# Communication.net
KiCad netlist of a schematic drawn in Altium Designer
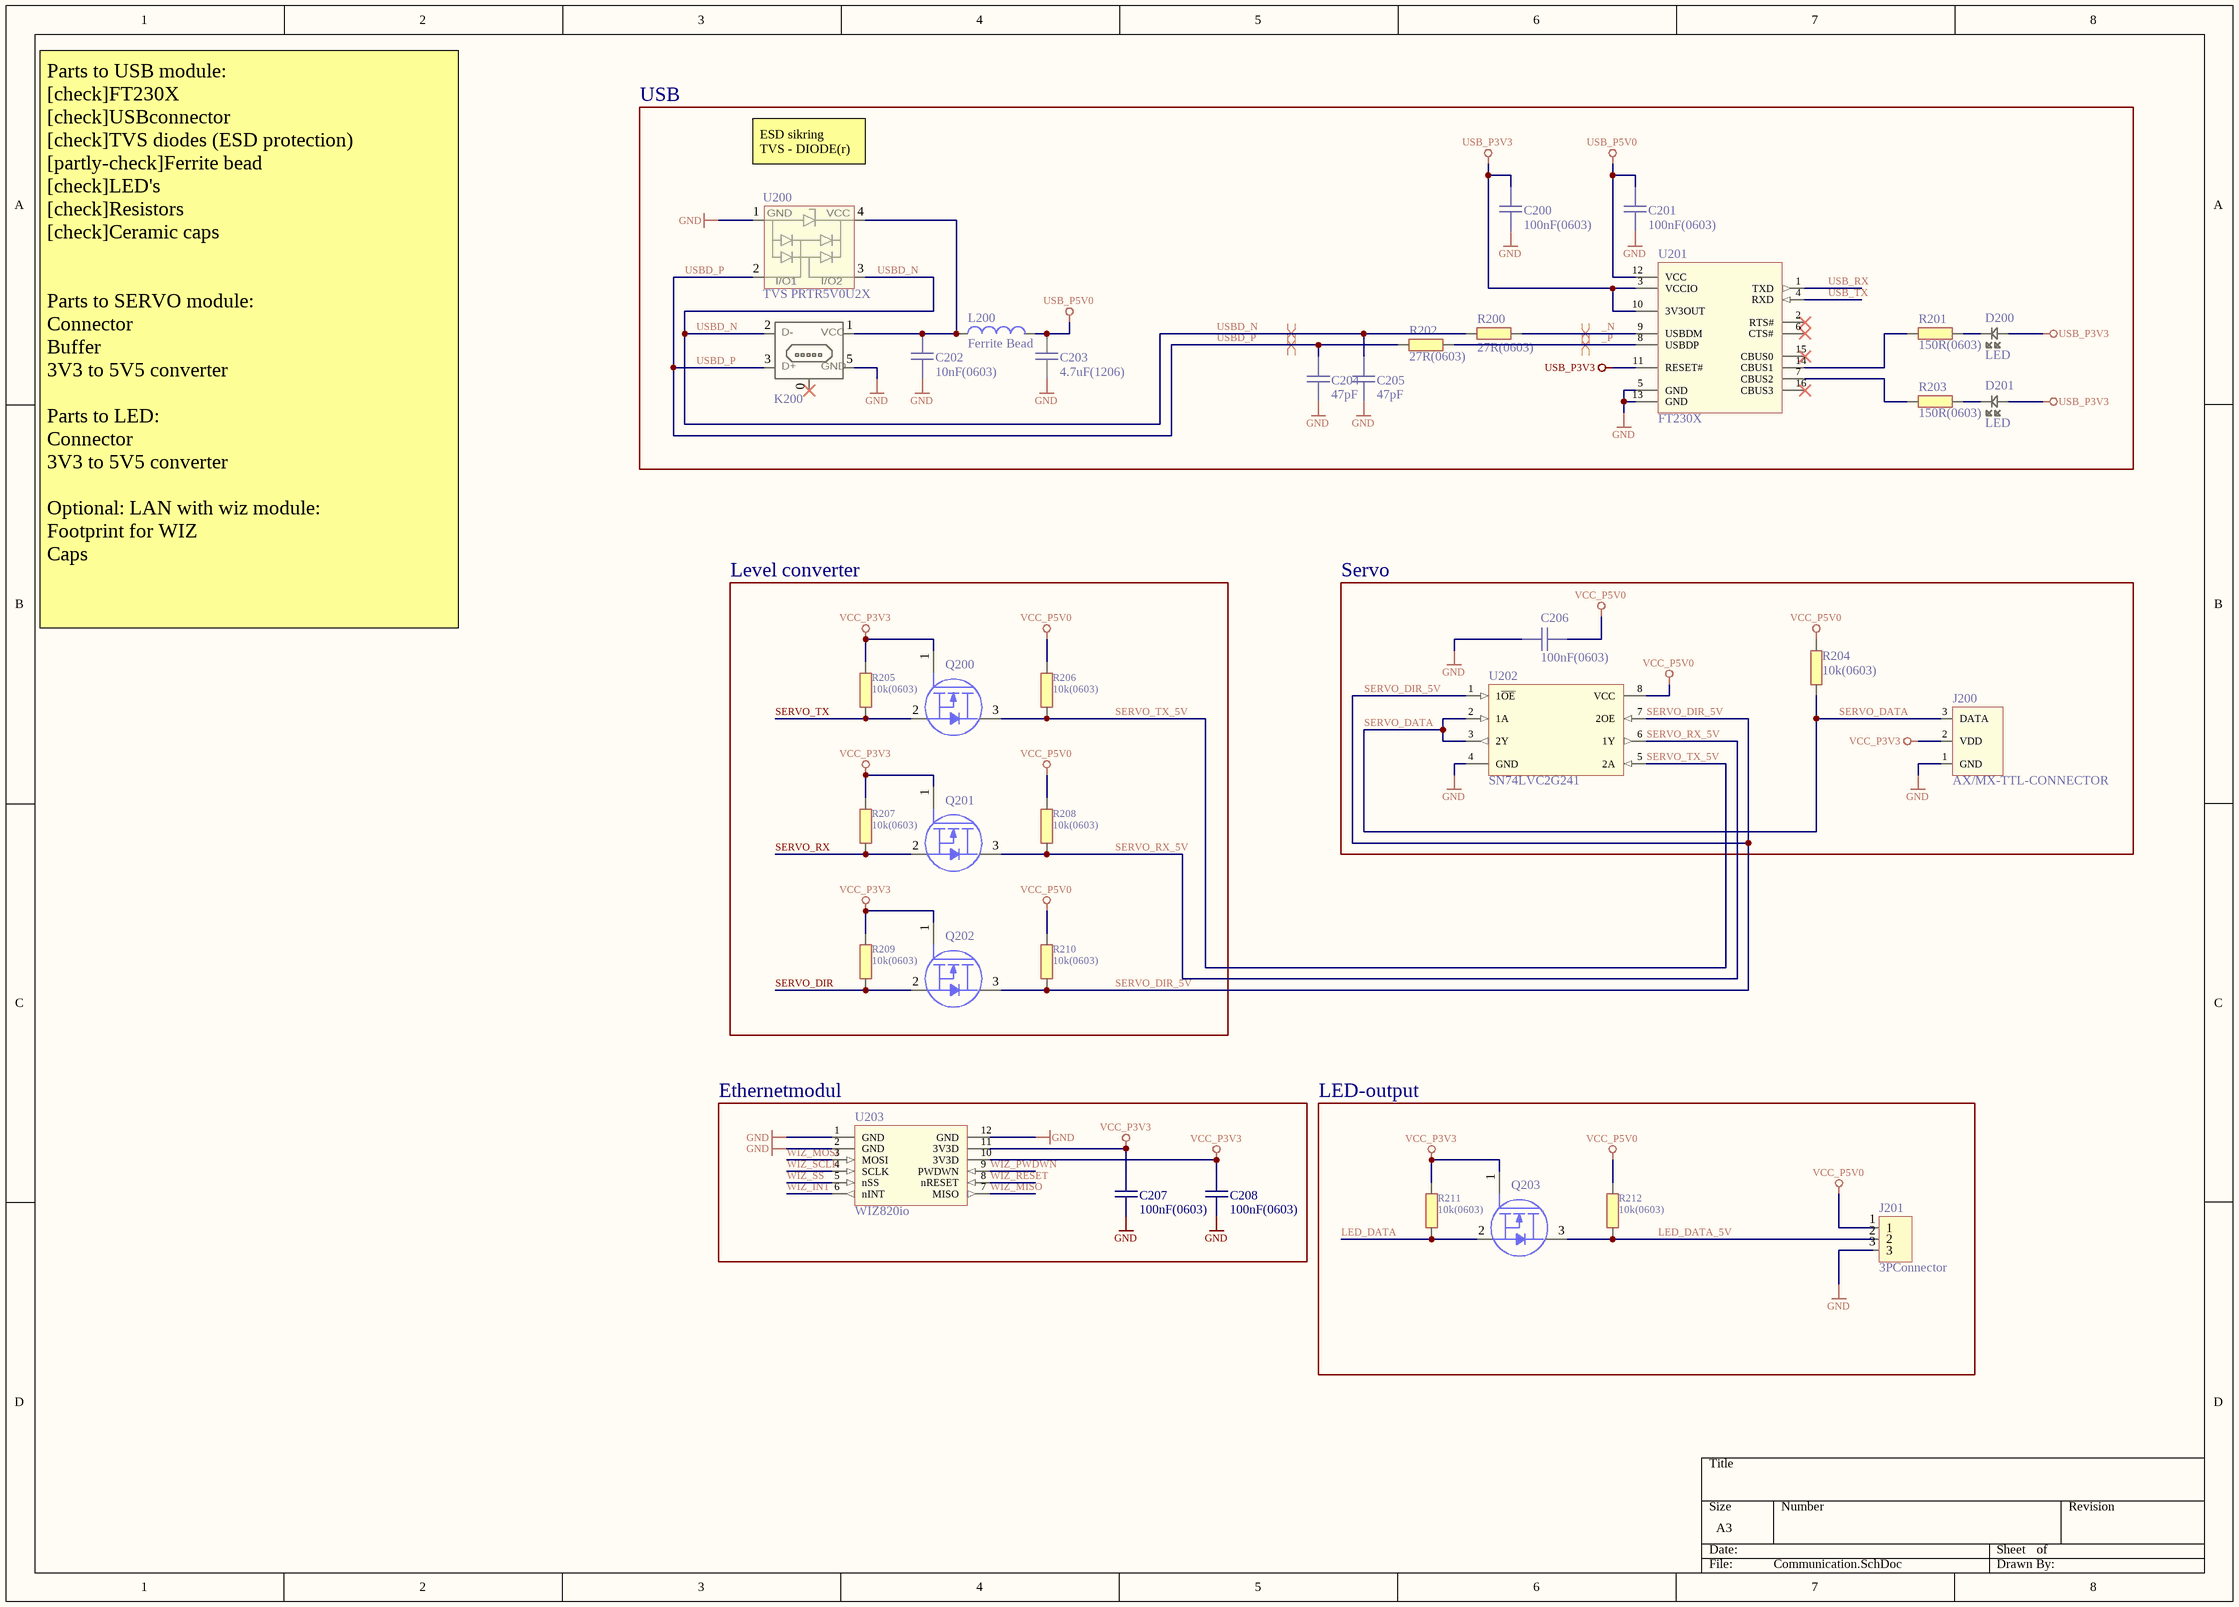
[diagram p0: Communication.SchDoc]

(export (version "E")
  (design (tool "Eeschema 10.0.6"))
  (components
    (comp (ref "C200")
      (value "100nF(0603)")
      (footprint "CAPC0603(1608)55_N")
      (description "100nF 0603 5% X7R 50V")
      (libsource (lib "OVLib") (part "CAP"))
    )
    (comp (ref "C201")
      (value "100nF(0603)")
      (footprint "CAPC0603(1608)55_N")
      (description "100nF 0603 5% X7R 50V")
      (libsource (lib "OVLib") (part "CAP"))
    )
    (comp (ref "C202")
      (value "10nF(0603)")
      (footprint "CAPC0603(1608)55_N")
      (description "0603 5% NP0 50V")
      (libsource (lib "OVLib") (part "CAP"))
    )
    (comp (ref "C203")
      (value "4.7uF(1206)")
      (footprint "CAPC1206(3216)170_N")
      (description "1206 chip X7R 50V")
      (libsource (lib "OVLib") (part "CAP"))
    )
    (comp (ref "C204")
      (value "47pF")
      (footprint "CAPC0603(1608)55_N")
      (description "0603 5% NP0 50V")
      (libsource (lib "OVLib") (part "CAP"))
    )
    (comp (ref "C205")
      (value "47pF")
      (footprint "CAPC0603(1608)55_N")
      (description "0603 5% NP0 50V")
      (libsource (lib "OVLib") (part "CAP"))
    )
    (comp (ref "C206")
      (value "100nF(0603)")
      (footprint "CAPC0603(1608)55_N")
      (description "100nF 0603 5% X7R 50V")
      (libsource (lib "OVLib") (part "CAP"))
    )
    (comp (ref "C207")
      (value "100nF(0603)")
      (footprint "CAPC0603(1608)55_N")
      (description "100nF 0603 5% X7R 50V")
      (libsource (lib "OVLib") (part "CAP"))
    )
    (comp (ref "C208")
      (value "100nF(0603)")
      (footprint "CAPC0603(1608)55_N")
      (description "100nF 0603 5% X7R 50V")
      (libsource (lib "OVLib") (part "CAP"))
    )
    (comp (ref "D200")
      (value "LED")
      (footprint "I_LEDC0603(1608)_N")
      (description "SMD")
      (libsource (lib "OVLib") (part "LED"))
    )
    (comp (ref "D201")
      (value "LED")
      (footprint "I_LEDC0603(1608)_N")
      (description "SMD")
      (libsource (lib "OVLib") (part "LED"))
    )
    (comp (ref "J200")
      (value "AX/MX-TTL-CONNECTOR")
      (footprint "MOLEX_22-03-5035")
      (description "Dynamixel AX/MX-Series servo connector 3 pin TTL version")
      (fields (field (name "MPN") "22-03-5035"))
      (libsource (lib "AX_MX-TTL-CONNECTOR") (part "AX/MX-TTL-CONNECTOR"))
    )
    (comp (ref "J201")
      (value "3PConnector")
      (footprint "JST_3P")
      (description "pris pr. stk.")
      (libsource (lib "OVLib") (part "3PConnector"))
    )
    (comp (ref "K200")
      (value "USB-OTG")
      (footprint "MILL-MAX_897-43-005-00-100001")
      (description "MINI USB B DEVICE CONNECTOR MOLEX 51387-0571")
      (fields
        (field (name "MANUFACTURER") "Mill-Max Manufacturing Corp.")
        (field (name "MPN") "897-43-005-00-100001")
      )
      (libsource (lib "MILL-MAX_897-43-005-00-100001") (part "MILL-MAX_897-43-005-00-100001"))
    )
    (comp (ref "L200")
      (value "Ferrite Bead")
      (footprint "0603")
      (description "Ferrite Bead 0603")
      (fields (field (name "MPN") "BLM18SG331TN1D"))
      (libsource (lib "BLM18SG331TN1D") (part "BLM18SG331TN1D"))
    )
    (comp (ref "Q200")
      (value "MOSFET_N_GSD")
      (footprint "SOT323P130X100-3_N")
      (description "N-Channel MOSFET 300mA")
      (libsource (lib "OVLib") (part "MOSFET_N_GSD"))
    )
    (comp (ref "Q201")
      (value "MOSFET_N_GSD")
      (footprint "SOT323P130X100-3_N")
      (description "N-Channel MOSFET 300mA")
      (libsource (lib "OVLib") (part "MOSFET_N_GSD"))
    )
    (comp (ref "Q202")
      (value "MOSFET_N_GSD")
      (footprint "SOT323P130X100-3_N")
      (description "N-Channel MOSFET 300mA")
      (libsource (lib "OVLib") (part "MOSFET_N_GSD"))
    )
    (comp (ref "Q203")
      (value "MOSFET_N_GSD")
      (footprint "SOT323P130X100-3_N")
      (description "N-Channel MOSFET 300mA")
      (libsource (lib "OVLib") (part "MOSFET_N_GSD"))
    )
    (comp (ref "R200")
      (value "27R(0603)")
      (footprint "RESC0603(1608)_N")
      (description "0603 0.1W 1% Thick film resistor")
      (libsource (lib "") (part "Resistor2_2"))
    )
    (comp (ref "R201")
      (value "150R(0603)")
      (footprint "RESC0603(1608)_N")
      (description "0603 0.1W 1% Thick film resistor")
      (libsource (lib "") (part "Resistor2_3"))
    )
    (comp (ref "R202")
      (value "27R(0603)")
      (footprint "RESC0603(1608)_N")
      (description "0603 0.1W 1% Thick film resistor")
      (libsource (lib "") (part "Resistor2_2"))
    )
    (comp (ref "R203")
      (value "150R(0603)")
      (footprint "RESC0603(1608)_N")
      (description "0603 0.1W 1% Thick film resistor")
      (libsource (lib "") (part "Resistor2_3"))
    )
    (comp (ref "R204")
      (value "10k(0603)")
      (footprint "RESC0603(1608)_N")
      (description "10k 0603 0.1W 1% Thick film resistor")
      (libsource (lib "OVLib") (part "Resistor2"))
    )
    (comp (ref "R205")
      (value "10k(0603)")
      (footprint "RESC0603(1608)_N")
      (description "10k 0603 0.1W 1% Thick film resistor")
      (libsource (lib "") (part "Resistor2_1"))
    )
    (comp (ref "R206")
      (value "10k(0603)")
      (footprint "RESC0603(1608)_N")
      (description "10k 0603 0.1W 1% Thick film resistor")
      (libsource (lib "") (part "Resistor2_1"))
    )
    (comp (ref "R207")
      (value "10k(0603)")
      (footprint "RESC0603(1608)_N")
      (description "10k 0603 0.1W 1% Thick film resistor")
      (libsource (lib "") (part "Resistor2_1"))
    )
    (comp (ref "R208")
      (value "10k(0603)")
      (footprint "RESC0603(1608)_N")
      (description "10k 0603 0.1W 1% Thick film resistor")
      (libsource (lib "") (part "Resistor2_1"))
    )
    (comp (ref "R209")
      (value "10k(0603)")
      (footprint "RESC0603(1608)_N")
      (description "10k 0603 0.1W 1% Thick film resistor")
      (libsource (lib "") (part "Resistor2_1"))
    )
    (comp (ref "R210")
      (value "10k(0603)")
      (footprint "RESC0603(1608)_N")
      (description "10k 0603 0.1W 1% Thick film resistor")
      (libsource (lib "") (part "Resistor2_1"))
    )
    (comp (ref "R211")
      (value "10k(0603)")
      (footprint "RESC0603(1608)_N")
      (description "10k 0603 0.1W 1% Thick film resistor")
      (libsource (lib "") (part "Resistor2_1"))
    )
    (comp (ref "R212")
      (value "10k(0603)")
      (footprint "RESC0603(1608)_N")
      (description "10k 0603 0.1W 1% Thick film resistor")
      (libsource (lib "") (part "Resistor2_1"))
    )
    (comp (ref "U200")
      (value "TVS PRTR5V0U2X")
      (footprint "SOT143B-M")
      (description "TVS Didode dual PRTR5V0U2X")
      (fields (field (name "MPN") "PRTR5V0U2X") (field (name "MANUFACTURER") "NXP"))
      (libsource (lib "PRTR5V0U2X") (part "PRTR5V0U2X"))
    )
    (comp (ref "U201")
      (value "FT230X")
      (footprint "SOP0635P4800-16N")
      (description "IC USB SERIAL BASIC UART 16SSOP")
      (fields
        (field (name "MPN") "FT230XS-R")
        (field (name "MANUFACTURER") "FTDI, Future Technology Devices International Ltd")
      )
      (libsource (lib "FT230XS") (part "FT230X"))
    )
    (comp (ref "U202")
      (value "SN74LVC2G241")
      (footprint "TSOP65P400X130-8N")
      (description "Dual  Buffer/Driver  With  3-State  Outputs, designed for 1.65-5.5Vcc operation")
      (fields (field (name "MANUFACTURER") "Texas Instruments") (field (name "MPN") "SN74LVC2G241DCUR"))
      (libsource (lib "SN74LVC2G241") (part "SN74LVC2G241"))
    )
    (comp (ref "U203")
      (value "WIZ820io")
      (footprint "Wiz820io")
      (description "WIZ820io, Ethernet module with W5200 module onboard and MAG-JACK")
      (fields (field (name "MPN") "WIZ820IO") (field (name "MANUFACTURER") "WIZnet"))
      (libsource (lib "WIZ820io") (part "WIZ820io"))
    )
  )
  (nets
    (net (code "1") (name "/LED_DATA") (class "Default")
      (node (ref "Q203") (pin "2") (pinfunction "Source_2") (pintype "passive"))
      (node (ref "R211") (pin "2") (pinfunction "2_2") (pintype "passive"))
    )
    (net (code "2") (name "/LED_DATA_5V") (class "Default")
      (node (ref "J201") (pin "2") (pinfunction "2_2") (pintype "passive"))
      (node (ref "Q203") (pin "3") (pinfunction "Drain_3") (pintype "passive"))
      (node (ref "R212") (pin "2") (pinfunction "2_2") (pintype "passive"))
    )
    (net (code "3") (name "/SERVO_DATA") (class "Default")
      (node (ref "J200") (pin "3") (pinfunction "DATA_3") (pintype "passive"))
      (node (ref "R204") (pin "1") (pinfunction "1_1") (pintype "passive"))
      (node (ref "U202") (pin "2") (pinfunction "1A_2") (pintype "input"))
      (node (ref "U202") (pin "3") (pinfunction "2Y_3") (pintype "output"))
    )
    (net (code "4") (name "/SERVO_DIR") (class "Default")
      (node (ref "Q202") (pin "2") (pinfunction "Source_2") (pintype "passive"))
      (node (ref "R209") (pin "2") (pinfunction "2_2") (pintype "passive"))
    )
    (net (code "5") (name "/SERVO_DIR_5V") (class "Default")
      (node (ref "Q202") (pin "3") (pinfunction "Drain_3") (pintype "passive"))
      (node (ref "R210") (pin "2") (pinfunction "2_2") (pintype "passive"))
      (node (ref "U202") (pin "1") (pinfunction "1~{OE}_1") (pintype "input"))
      (node (ref "U202") (pin "7") (pinfunction "2OE_7") (pintype "input"))
    )
    (net (code "6") (name "/SERVO_RX") (class "Default")
      (node (ref "Q201") (pin "2") (pinfunction "Source_2") (pintype "passive"))
      (node (ref "R207") (pin "2") (pinfunction "2_2") (pintype "passive"))
    )
    (net (code "7") (name "/SERVO_RX_5V") (class "Default")
      (node (ref "Q201") (pin "3") (pinfunction "Drain_3") (pintype "passive"))
      (node (ref "R208") (pin "2") (pinfunction "2_2") (pintype "passive"))
      (node (ref "U202") (pin "6") (pinfunction "1Y_6") (pintype "output"))
    )
    (net (code "8") (name "/SERVO_TX") (class "Default")
      (node (ref "Q200") (pin "2") (pinfunction "Source_2") (pintype "passive"))
      (node (ref "R205") (pin "2") (pinfunction "2_2") (pintype "passive"))
    )
    (net (code "9") (name "/SERVO_TX_5V") (class "Default")
      (node (ref "Q200") (pin "3") (pinfunction "Drain_3") (pintype "passive"))
      (node (ref "R206") (pin "2") (pinfunction "2_2") (pintype "passive"))
      (node (ref "U202") (pin "5") (pinfunction "2A_5") (pintype "input"))
    )
    (net (code "10") (name "/USBD_N") (class "Default")
      (node (ref "C205") (pin "2") (pinfunction "2_2") (pintype "passive"))
      (node (ref "K200") (pin "2") (pinfunction "D-_2") (pintype "passive"))
      (node (ref "R200") (pin "1") (pinfunction "1_1") (pintype "passive"))
      (node (ref "U200") (pin "3") (pinfunction "I/O2_3") (pintype "passive"))
    )
    (net (code "11") (name "/USBD_P") (class "Default")
      (node (ref "C204") (pin "2") (pinfunction "2_2") (pintype "passive"))
      (node (ref "K200") (pin "3") (pinfunction "D+_3") (pintype "passive"))
      (node (ref "R202") (pin "1") (pinfunction "1_1") (pintype "passive"))
      (node (ref "U200") (pin "2") (pinfunction "I/O1_2") (pintype "passive"))
    )
    (net (code "12") (name "/USB_RX") (class "Default")
      (node (ref "U201") (pin "1") (pinfunction "TXD_1") (pintype "output"))
    )
    (net (code "13") (name "/USB_TX") (class "Default")
      (node (ref "U201") (pin "4") (pinfunction "RXD_4") (pintype "input"))
    )
    (net (code "14") (name "/WIZ_INT") (class "Default")
      (node (ref "U203") (pin "6") (pinfunction "nINT_6") (pintype "output"))
    )
    (net (code "15") (name "/WIZ_MISO") (class "Default")
      (node (ref "U203") (pin "7") (pinfunction "MISO_7") (pintype "output"))
    )
    (net (code "16") (name "/WIZ_MOSI") (class "Default")
      (node (ref "U203") (pin "3") (pinfunction "MOSI_3") (pintype "input"))
    )
    (net (code "17") (name "/WIZ_PWDWN") (class "Default")
      (node (ref "U203") (pin "9") (pinfunction "PWDWN_9") (pintype "input"))
    )
    (net (code "18") (name "/WIZ_RESET") (class "Default")
      (node (ref "U203") (pin "8") (pinfunction "nRESET_8") (pintype "input"))
    )
    (net (code "19") (name "/WIZ_SCLK") (class "Default")
      (node (ref "U203") (pin "4") (pinfunction "SCLK_4") (pintype "input"))
    )
    (net (code "20") (name "/WIZ_SS") (class "Default")
      (node (ref "U203") (pin "5") (pinfunction "nSS_5") (pintype "input"))
    )
    (net (code "21") (name "/_N") (class "Default")
      (node (ref "R200") (pin "2") (pinfunction "2_2") (pintype "passive"))
      (node (ref "U201") (pin "9") (pinfunction "USBDM_9") (pintype "passive"))
    )
    (net (code "22") (name "/_P") (class "Default")
      (node (ref "R202") (pin "2") (pinfunction "2_2") (pintype "passive"))
      (node (ref "U201") (pin "8") (pinfunction "USBDP_8") (pintype "passive"))
    )
    (net (code "23") (name "GND") (class "Default")
      (node (ref "C200") (pin "1") (pinfunction "1_1") (pintype "passive"))
      (node (ref "C201") (pin "1") (pinfunction "1_1") (pintype "passive"))
      (node (ref "C202") (pin "1") (pinfunction "1_1") (pintype "passive"))
      (node (ref "C203") (pin "1") (pinfunction "1_1") (pintype "passive"))
      (node (ref "C204") (pin "1") (pinfunction "1_1") (pintype "passive"))
      (node (ref "C205") (pin "1") (pinfunction "1_1") (pintype "passive"))
      (node (ref "C206") (pin "1") (pinfunction "1_1") (pintype "passive"))
      (node (ref "C207") (pin "1") (pinfunction "1_1") (pintype "passive"))
      (node (ref "C208") (pin "1") (pinfunction "1_1") (pintype "passive"))
      (node (ref "J200") (pin "1") (pinfunction "GND_1") (pintype "passive"))
      (node (ref "J201") (pin "3") (pinfunction "3_3") (pintype "passive"))
      (node (ref "K200") (pin "5") (pinfunction "GD_5") (pintype "passive"))
      (node (ref "U200") (pin "1") (pinfunction "GND_1") (pintype "passive"))
      (node (ref "U201") (pin "13") (pinfunction "GND_13") (pintype "passive"))
      (node (ref "U201") (pin "5") (pinfunction "GND_5") (pintype "passive"))
      (node (ref "U202") (pin "4") (pinfunction "GND_4") (pintype "power_in"))
      (node (ref "U203") (pin "1") (pinfunction "GND_1") (pintype "passive"))
      (node (ref "U203") (pin "12") (pinfunction "GND_12") (pintype "passive"))
      (node (ref "U203") (pin "2") (pinfunction "GND_2") (pintype "passive"))
    )
    (net (code "24") (name "Net-(D200-Pad2)") (class "Default")
      (node (ref "D200") (pin "2") (pinfunction "2_2") (pintype "passive"))
      (node (ref "R201") (pin "1") (pinfunction "1_1") (pintype "passive"))
    )
    (net (code "25") (name "Net-(D201-Pad2)") (class "Default")
      (node (ref "D201") (pin "2") (pinfunction "2_2") (pintype "passive"))
      (node (ref "R203") (pin "1") (pinfunction "1_1") (pintype "passive"))
    )
    (net (code "26") (name "Net-(K200-VB)") (class "Default")
      (node (ref "C202") (pin "2") (pinfunction "2_2") (pintype "passive"))
      (node (ref "K200") (pin "1") (pinfunction "VB_1") (pintype "passive"))
      (node (ref "L200") (pin "1") (pintype "passive"))
      (node (ref "U200") (pin "4") (pinfunction "VCC_4") (pintype "passive"))
    )
    (net (code "27") (name "Net-(U201-CBUS1)") (class "Default")
      (node (ref "R201") (pin "2") (pinfunction "2_2") (pintype "passive"))
      (node (ref "U201") (pin "14") (pinfunction "CBUS1_14") (pintype "passive"))
    )
    (net (code "28") (name "Net-(U201-CBUS2)") (class "Default")
      (node (ref "R203") (pin "2") (pinfunction "2_2") (pintype "passive"))
      (node (ref "U201") (pin "7") (pinfunction "CBUS2_7") (pintype "passive"))
    )
    (net (code "29") (name "USB_P3V3") (class "Default")
      (node (ref "C200") (pin "2") (pinfunction "2_2") (pintype "passive"))
      (node (ref "D200") (pin "1") (pinfunction "1_1") (pintype "passive"))
      (node (ref "D201") (pin "1") (pinfunction "1_1") (pintype "passive"))
      (node (ref "U201") (pin "10") (pinfunction "3V3OUT_10") (pintype "passive"))
      (node (ref "U201") (pin "11") (pinfunction "RESET#_11") (pintype "passive"))
      (node (ref "U201") (pin "3") (pinfunction "VCCIO_3") (pintype "passive"))
    )
    (net (code "30") (name "USB_P5V0") (class "Default")
      (node (ref "C201") (pin "2") (pinfunction "2_2") (pintype "passive"))
      (node (ref "C203") (pin "2") (pinfunction "2_2") (pintype "passive"))
      (node (ref "L200") (pin "2") (pintype "passive"))
      (node (ref "U201") (pin "12") (pinfunction "VCC_12") (pintype "passive"))
    )
    (net (code "31") (name "VCC_P3V3") (class "Default")
      (node (ref "C207") (pin "2") (pinfunction "2_2") (pintype "passive"))
      (node (ref "C208") (pin "2") (pinfunction "2_2") (pintype "passive"))
      (node (ref "J200") (pin "2") (pinfunction "VDD_2") (pintype "passive"))
      (node (ref "Q200") (pin "1") (pinfunction "Gate_1") (pintype "passive"))
      (node (ref "Q201") (pin "1") (pinfunction "Gate_1") (pintype "passive"))
      (node (ref "Q202") (pin "1") (pinfunction "Gate_1") (pintype "passive"))
      (node (ref "Q203") (pin "1") (pinfunction "Gate_1") (pintype "passive"))
      (node (ref "R205") (pin "1") (pinfunction "1_1") (pintype "passive"))
      (node (ref "R207") (pin "1") (pinfunction "1_1") (pintype "passive"))
      (node (ref "R209") (pin "1") (pinfunction "1_1") (pintype "passive"))
      (node (ref "R211") (pin "1") (pinfunction "1_1") (pintype "passive"))
      (node (ref "U203") (pin "10") (pinfunction "3V3D_10") (pintype "passive"))
      (node (ref "U203") (pin "11") (pinfunction "3V3D_11") (pintype "passive"))
    )
    (net (code "32") (name "VCC_P5V0") (class "Default")
      (node (ref "C206") (pin "2") (pinfunction "2_2") (pintype "passive"))
      (node (ref "J201") (pin "1") (pinfunction "1_1") (pintype "passive"))
      (node (ref "R204") (pin "2") (pinfunction "2_2") (pintype "passive"))
      (node (ref "R206") (pin "1") (pinfunction "1_1") (pintype "passive"))
      (node (ref "R208") (pin "1") (pinfunction "1_1") (pintype "passive"))
      (node (ref "R210") (pin "1") (pinfunction "1_1") (pintype "passive"))
      (node (ref "R212") (pin "1") (pinfunction "1_1") (pintype "passive"))
      (node (ref "U202") (pin "8") (pinfunction "VCC_8") (pintype "power_in"))
    )
    (net (code "33") (name "unconnected-(K200-Shield-Pad0)") (class "Default")
      (node (ref "K200") (pin "0") (pinfunction "Shield_0") (pintype "passive+no_connect"))
    )
    (net (code "34") (name "unconnected-(U201-CBUS0-Pad15)") (class "Default")
      (node (ref "U201") (pin "15") (pinfunction "CBUS0_15") (pintype "passive+no_connect"))
    )
    (net (code "35") (name "unconnected-(U201-CBUS3-Pad16)") (class "Default")
      (node (ref "U201") (pin "16") (pinfunction "CBUS3_16") (pintype "passive+no_connect"))
    )
    (net (code "36") (name "unconnected-(U201-CTS#-Pad6)") (class "Default")
      (node (ref "U201") (pin "6") (pinfunction "CTS#_6") (pintype "passive+no_connect"))
    )
    (net (code "37") (name "unconnected-(U201-RTS#-Pad2)") (class "Default")
      (node (ref "U201") (pin "2") (pinfunction "RTS#_2") (pintype "passive+no_connect"))
    )
  )
)
